# 3V3_LDO.net
KiCad netlist of a schematic drawn in Altium Designer
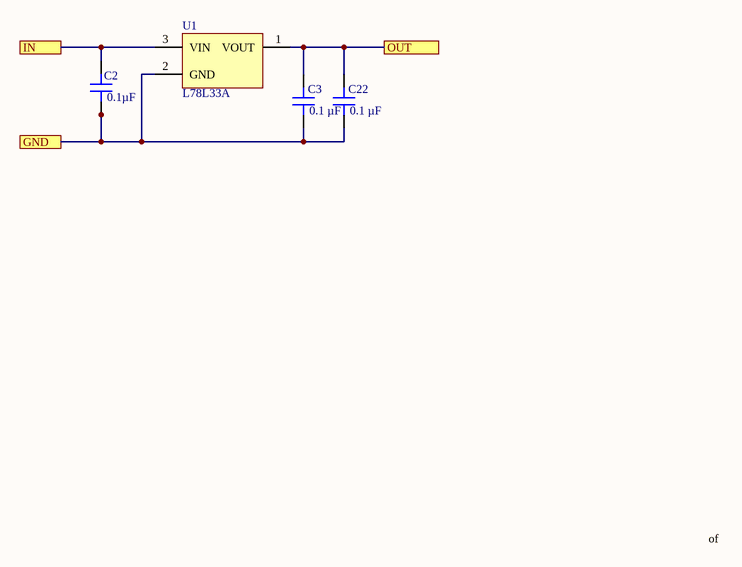
[diagram p0: 3V3_LDO.SchDoc]

(export (version "E")
  (design (tool "Eeschema 10.0.6"))
  (components
    (comp (ref "C2")
      (value "0.1µF")
      (footprint "CAP 0603_1608")
      (description "CAP CER 0.1UF 100V 0603 EPOXY")
      (fields
        (field (name "PART NUMBER") "GCG188R92A104KA03D")
        (field (name "MANUFACTURER") "Murata Electronics")
      )
      (libsource (lib "Celestial Altium Library - altium_library") (part "Capacitor"))
    )
    (comp (ref "C3")
      (value "0.1 µF")
      (footprint "CAP 0402_1005")
      (description "CAP CER 0.1UF 16V X7R 0402")
      (fields (field (name "PART NUMBER") "C0402C104K4RACAUTO") (field (name "MANUFACTURER") "KEMET"))
      (libsource (lib "Celestial Altium Library - altium_library") (part "Capacitor"))
    )
    (comp (ref "C22")
      (value "0.1 µF")
      (footprint "CAP 0402_1005")
      (description "CAP CER 0.1UF 16V X7R 0402")
      (fields (field (name "PART NUMBER") "C0402C104K4RACAUTO") (field (name "MANUFACTURER") "KEMET"))
      (libsource (lib "Celestial Altium Library - altium_library") (part "Capacitor"))
    )
    (comp (ref "U1")
      (value "L78L33A")
      (footprint "SOT-89-3")
      (description "3.3V LDO")
      (libsource (lib "IC") (part "L78L33A"))
    )
  )
  (nets
    (net (code "1") (name "/GND") (class "Default")
      (node (ref "C2") (pin "2") (pinfunction "2_2") (pintype "passive"))
      (node (ref "C22") (pin "1") (pinfunction "1_1") (pintype "passive"))
      (node (ref "C3") (pin "1") (pinfunction "1_1") (pintype "passive"))
      (node (ref "U1") (pin "2") (pinfunction "GND_2") (pintype "passive"))
    )
    (net (code "2") (name "/IN") (class "Default")
      (node (ref "C2") (pin "1") (pinfunction "1_1") (pintype "passive"))
      (node (ref "U1") (pin "3") (pinfunction "VIN_3") (pintype "passive"))
    )
    (net (code "3") (name "/OUT") (class "Default")
      (node (ref "C22") (pin "2") (pinfunction "2_2") (pintype "passive"))
      (node (ref "C3") (pin "2") (pinfunction "2_2") (pintype "passive"))
      (node (ref "U1") (pin "1") (pinfunction "VOUT_1") (pintype "passive"))
    )
  )
)
